# HS_Inverted-Normal_Switch_LOW_PWR.net
KiCad netlist of a schematic drawn in Altium Designer
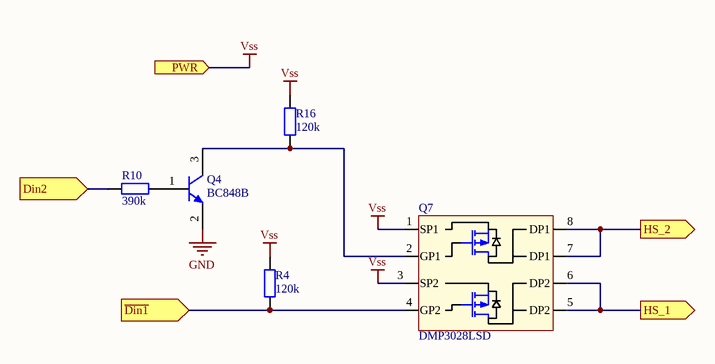
[diagram p0: HS_Inverted-Normal_Switch_LOW_PWR.SchDoc]

(export (version "E")
  (design (tool "Eeschema 10.0.6"))
  (components
    (comp (ref "Q4")
      (value "BC848B")
      (footprint "SOT23_N")
      (description "NPN Silicon AF Transistor, 30 V VCEO, 100 mA IC, SOT23, Reel, Green")
      (fields (field (name "MANUFACTURER") "Infineon"))
      (libsource (lib "Datalogger") (part "BC848B"))
    )
    (comp (ref "Q7")
      (value "DMP3028LSD")
      (footprint "SOIC-8_SOIC127P600X175-8N")
      (description "MOSFET 2P-CH 30V 6A SO-8, VgMax=20V, Max Drain Resistance (38 mΩ)")
      (fields
        (field (name "MANUFACTURER") "Diodes")
        (field (name "MANUFACTURER PART NUMBER") "DMP3028LSD-13")
      )
      (libsource (lib "Datalogger") (part "DMP3028LSD"))
    )
    (comp (ref "R4")
      (value "120k")
      (footprint "RES-1206_M")
      (description "Resistor")
      (fields (field (name "PUBLISHER") "Altium Limited"))
      (libsource (lib "Datalogger") (part "Res2"))
    )
    (comp (ref "R10")
      (value "390k")
      (footprint "RES-1206_M")
      (description "Resistor")
      (fields (field (name "PUBLISHER") "Altium Limited"))
      (libsource (lib "") (part "Res2_1"))
    )
    (comp (ref "R16")
      (value "120k")
      (footprint "RES-1206_M")
      (description "Resistor")
      (fields (field (name "PUBLISHER") "Altium Limited"))
      (libsource (lib "Datalogger") (part "Res2"))
    )
  )
  (nets
    (net (code "1") (name "/Din2") (class "Default")
      (node (ref "R10") (pin "1") (pinfunction "1_1") (pintype "passive"))
    )
    (net (code "2") (name "/HS_1") (class "Default")
      (node (ref "Q7") (pin "5") (pinfunction "DP2_5") (pintype "passive"))
      (node (ref "Q7") (pin "6") (pinfunction "DP2_6") (pintype "passive"))
    )
    (net (code "3") (name "/HS_2") (class "Default")
      (node (ref "Q7") (pin "7") (pinfunction "DP1_7") (pintype "passive"))
      (node (ref "Q7") (pin "8") (pinfunction "DP1_8") (pintype "passive"))
    )
    (net (code "4") (name "/~{Din1}") (class "Default")
      (node (ref "Q7") (pin "4") (pinfunction "GP2_4") (pintype "passive"))
      (node (ref "R4") (pin "1") (pinfunction "1_1") (pintype "passive"))
    )
    (net (code "5") (name "GND") (class "Default")
      (node (ref "Q4") (pin "2") (pinfunction "E_2") (pintype "passive"))
    )
    (net (code "6") (name "Net-(Q4-B)") (class "Default")
      (node (ref "Q4") (pin "1") (pinfunction "B_1") (pintype "passive"))
      (node (ref "R10") (pin "2") (pinfunction "2_2") (pintype "passive"))
    )
    (net (code "7") (name "Net-(Q4-C)") (class "Default")
      (node (ref "Q4") (pin "3") (pinfunction "C_3") (pintype "passive"))
      (node (ref "Q7") (pin "2") (pinfunction "GP1_2") (pintype "passive"))
      (node (ref "R16") (pin "1") (pinfunction "1_1") (pintype "passive"))
    )
    (net (code "8") (name "Vss") (class "Default")
      (node (ref "Q7") (pin "1") (pinfunction "SP1_1") (pintype "passive"))
      (node (ref "Q7") (pin "3") (pinfunction "SP2_3") (pintype "passive"))
      (node (ref "R16") (pin "2") (pinfunction "2_2") (pintype "passive"))
      (node (ref "R4") (pin "2") (pinfunction "2_2") (pintype "passive"))
    )
  )
)
